# Motor-X.net
KiCad netlist of a schematic drawn in Altium Designer
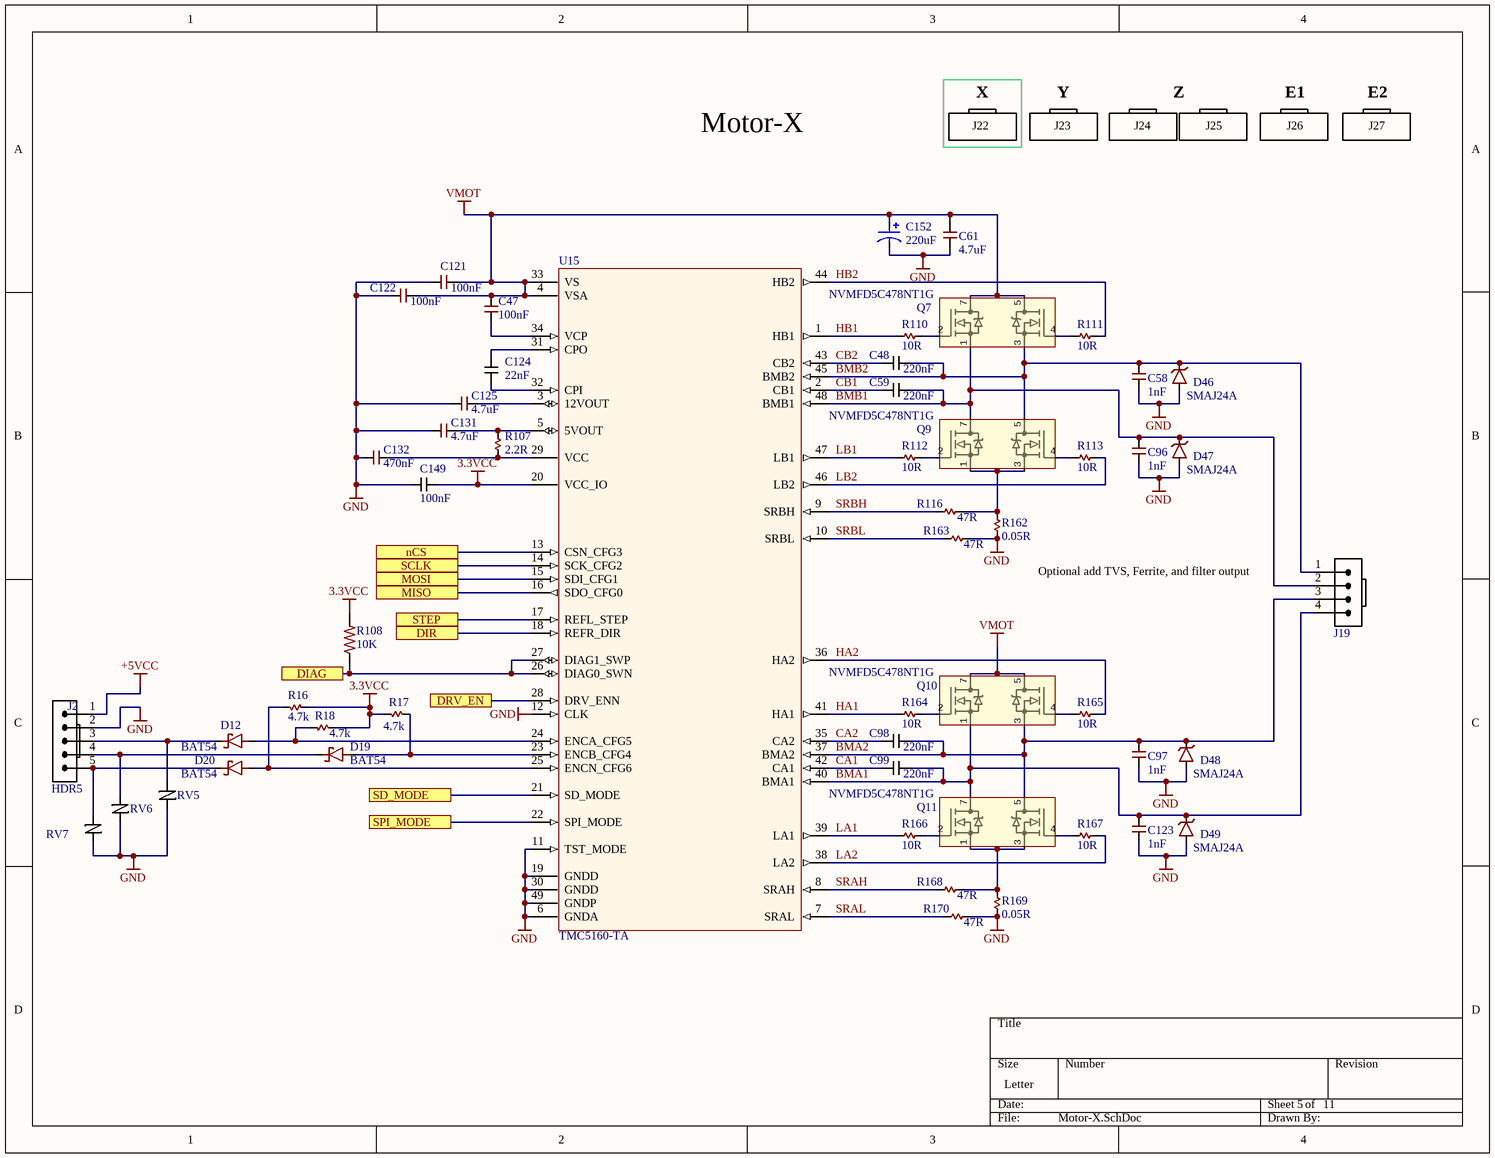
[diagram p0: Motor-X.SchDoc]

(export (version "E")
  (design (tool "Eeschema 10.0.6"))
  (components
    (comp (ref "C47")
      (value "100nF")
      (footprint "C0603")
      (description "CAP CER 0603 100nF 50V 10% X7R")
      (fields (field (name "MANUFACTURER") "Kemet") (field (name "PART") "100nF 50V X7R 0603"))
      (libsource (lib "Capacitors") (part "100nF 0603 50V X7R"))
    )
    (comp (ref "C48")
      (value "220nF")
      (footprint "C0603")
      (description "CAP CER 0.22UF 50V X7R 0603")
      (fields (field (name "MANUFACTURER") "TDK"))
      (libsource (lib "Capacitors") (part "220nF 50V X7R 0603"))
    )
    (comp (ref "C58")
      (value "1nF")
      (footprint "C0603")
      (description "CAP CER 0603  1nF 50v 10% X7R")
      (fields (field (name "MANUFACTURER") "Kemet") (field (name "TOLERANCE") "+/- 10%"))
      (libsource (lib "Capacitors") (part "1nF 50V X7R 0603"))
    )
    (comp (ref "C59")
      (value "220nF")
      (footprint "C0603")
      (description "CAP CER 0.22UF 50V X7R 0603")
      (fields (field (name "MANUFACTURER") "TDK"))
      (libsource (lib "Capacitors") (part "220nF 50V X7R 0603"))
    )
    (comp (ref "C61")
      (value "4.7uF")
      (footprint "C1206")
      (description "CAP CER 1206 4.7uF 50V 10% X5R")
      (fields (field (name "MANUFACTURER") "Kemet") (field (name "PART") "4.7uF 50V X5R 1206"))
      (libsource (lib "Capacitors") (part "4.7uF 1206 50V X5R"))
    )
    (comp (ref "C96")
      (value "1nF")
      (footprint "C0603")
      (description "CAP CER 0603  1nF 50v 10% X7R")
      (fields (field (name "MANUFACTURER") "Kemet") (field (name "TOLERANCE") "+/- 10%"))
      (libsource (lib "Capacitors") (part "1nF 50V X7R 0603"))
    )
    (comp (ref "C97")
      (value "1nF")
      (footprint "C0603")
      (description "CAP CER 0603  1nF 50v 10% X7R")
      (fields (field (name "MANUFACTURER") "Kemet") (field (name "TOLERANCE") "+/- 10%"))
      (libsource (lib "Capacitors") (part "1nF 50V X7R 0603"))
    )
    (comp (ref "C98")
      (value "220nF")
      (footprint "C0603")
      (description "CAP CER 0.22UF 50V X7R 0603")
      (fields (field (name "MANUFACTURER") "TDK"))
      (libsource (lib "Capacitors") (part "220nF 50V X7R 0603"))
    )
    (comp (ref "C99")
      (value "220nF")
      (footprint "C0603")
      (description "CAP CER 0.22UF 50V X7R 0603")
      (fields (field (name "MANUFACTURER") "TDK"))
      (libsource (lib "Capacitors") (part "220nF 50V X7R 0603"))
    )
    (comp (ref "C121")
      (value "100nF")
      (footprint "C0603")
      (description "CAP CER 0603 100nF 50V 10% X7R")
      (fields (field (name "MANUFACTURER") "Kemet") (field (name "PART") "100nF 50V X7R 0603"))
      (libsource (lib "Capacitors") (part "100nF 0603 50V X7R"))
    )
    (comp (ref "C122")
      (value "100nF")
      (footprint "C0603")
      (description "CAP CER 0603 100nF 50V 10% X7R")
      (fields (field (name "MANUFACTURER") "Kemet") (field (name "PART") "100nF 50V X7R 0603"))
      (libsource (lib "Capacitors") (part "100nF 0603 50V X7R"))
    )
    (comp (ref "C123")
      (value "1nF")
      (footprint "C0603")
      (description "CAP CER 0603  1nF 50v 10% X7R")
      (fields (field (name "MANUFACTURER") "Kemet") (field (name "TOLERANCE") "+/- 10%"))
      (libsource (lib "Capacitors") (part "1nF 50V X7R 0603"))
    )
    (comp (ref "C124")
      (value "22nF")
      (footprint "C0603")
      (description "CAP CER 0.022UF 100V X7R 0603")
      (fields (field (name "MANUFACTURER") "Kemet"))
      (libsource (lib "Capacitors") (part "22nF 100V X7R 0603"))
    )
    (comp (ref "C125")
      (value "4.7uF")
      (footprint "C1206")
      (description "CAP CER 1206 4.7uF 50V 10% X5R")
      (fields (field (name "MANUFACTURER") "Kemet") (field (name "PART") "4.7uF 50V X5R 1206"))
      (libsource (lib "Capacitors") (part "4.7uF 1206 50V X5R"))
    )
    (comp (ref "C131")
      (value "4.7uF")
      (footprint "C0603")
      (description "CAP CER 4.7UF 6.3V X7R 0603")
      (fields (field (name "MANUFACTURER") "Samsung") (field (name "TOLERANCE") "10%"))
      (libsource (lib "Capacitors") (part "4.7uF 0603 6.3V X7R"))
    )
    (comp (ref "C132")
      (value "470nF")
      (footprint "C0402")
      (description "470nF 6.3v C0402 - GRM155R60J474KE19D")
      (fields (field (name "TOLERANCE") "10%") (field (name "MANUFACTURER") "Murata"))
      (libsource (lib "Capacitors") (part "470nF 0402 6.3V X5R"))
    )
    (comp (ref "C149")
      (value "100nF")
      (footprint "C0201 Large Pads")
      (description "CAP CER 0.1UF 6.3V 10% X5R 0201")
      (fields (field (name "MANUFACTURER") "Samsung") (field (name "TOLERANCE") "10%"))
      (libsource (lib "Capacitors") (part "100nF 6.3V X5R 0201"))
    )
    (comp (ref "C152")
      (value "220uF")
      (footprint "CAP10X10")
      (description "CAP ALUM 220UF 20% 50V SMD")
      (fields (field (name "MANUFACTURER") "Nichicon") (field (name "TOLERANCE") "20%"))
      (libsource (lib "Capacitors") (part "220uF Al-El 50V"))
    )
    (comp (ref "D12")
      (value "BAT54")
      (footprint "SOD523_IPC")
      (description "DIODE SCHOTTKY 30V 200MA SOD523")
      (fields (field (name "MANUFACTURER") "Diodes Incorporated") (field (name "PART") "Schottky Diode"))
      (libsource (lib "Diodes") (part "BAT54WX"))
    )
    (comp (ref "D19")
      (value "BAT54")
      (footprint "SOD523_IPC")
      (description "DIODE SCHOTTKY 30V 200MA SOD523")
      (fields (field (name "MANUFACTURER") "Diodes Incorporated") (field (name "PART") "Schottky Diode"))
      (libsource (lib "Diodes") (part "BAT54WX"))
    )
    (comp (ref "D20")
      (value "BAT54")
      (footprint "SOD523_IPC")
      (description "DIODE SCHOTTKY 30V 200MA SOD523")
      (fields (field (name "MANUFACTURER") "Diodes Incorporated") (field (name "PART") "Schottky Diode"))
      (libsource (lib "Diodes") (part "BAT54WX"))
    )
    (comp (ref "D46")
      (value "SMAJ24A")
      (footprint "SMA-SM")
      (description "TVS DIODE 24V 38.9V SMA")
      (fields (field (name "MANUFACTURER") "Bourns Inc"))
      (libsource (lib "Diodes") (part "SMAJ24A"))
    )
    (comp (ref "D47")
      (value "SMAJ24A")
      (footprint "SMA-SM")
      (description "TVS DIODE 24V 38.9V SMA")
      (fields (field (name "MANUFACTURER") "Bourns Inc"))
      (libsource (lib "Diodes") (part "SMAJ24A"))
    )
    (comp (ref "D48")
      (value "SMAJ24A")
      (footprint "SMA-SM")
      (description "TVS DIODE 24V 38.9V SMA")
      (fields (field (name "MANUFACTURER") "Bourns Inc"))
      (libsource (lib "Diodes") (part "SMAJ24A"))
    )
    (comp (ref "D49")
      (value "SMAJ24A")
      (footprint "SMA-SM")
      (description "TVS DIODE 24V 38.9V SMA")
      (fields (field (name "MANUFACTURER") "Bourns Inc"))
      (libsource (lib "Diodes") (part "SMAJ24A"))
    )
    (comp (ref "J2")
      (value "HDR5")
      (footprint "70543-04_PIN-IN-PASTE")
      (description "5 Positions Header, Shrouded Connector 0.100\" (2.54mm) Through Hole Gold - Pin in Paste")
      (fields (field (name "MANUFACTURER") "Molex") (field (name "PART") "5 Pin Conn VERT"))
      (libsource (lib "Connectors") (part "CONN 5POS VERT 0.1{dblquote} SHRD LOCKING PIP"))
    )
    (comp (ref "J19")
      (value "Molex 0705430003")
      (footprint "4POL254 PIN-IN-PASTE")
      (description "Molex 4 Pin Clip Connector - Pin In Paste footprint")
      (libsource (lib "Connectors") (part "Molex 0705430003 PIP"))
    )
    (comp (ref "Q7")
      (value "NVMFD5C478NT1G")
      (footprint "SO8FL-Dual (DFN8 5x6, 1.26P Dual Flag)")
      (description "40V 17 MOHM T6 S08FL DUAL")
      (fields (field (name "MANUFACTURER") "ON Semiconductor") (field (name "TOLERANCE") "-NA-"))
      (libsource (lib "Transistors") (part "NVMFD5C478NT1G"))
    )
    (comp (ref "Q9")
      (value "NVMFD5C478NT1G")
      (footprint "SO8FL-Dual (DFN8 5x6, 1.26P Dual Flag)")
      (description "40V 17 MOHM T6 S08FL DUAL")
      (fields (field (name "MANUFACTURER") "ON Semiconductor") (field (name "TOLERANCE") "-NA-"))
      (libsource (lib "Transistors") (part "NVMFD5C478NT1G"))
    )
    (comp (ref "Q10")
      (value "NVMFD5C478NT1G")
      (footprint "SO8FL-Dual (DFN8 5x6, 1.26P Dual Flag)")
      (description "40V 17 MOHM T6 S08FL DUAL")
      (fields (field (name "MANUFACTURER") "ON Semiconductor") (field (name "TOLERANCE") "-NA-"))
      (libsource (lib "Transistors") (part "NVMFD5C478NT1G"))
    )
    (comp (ref "Q11")
      (value "NVMFD5C478NT1G")
      (footprint "SO8FL-Dual (DFN8 5x6, 1.26P Dual Flag)")
      (description "40V 17 MOHM T6 S08FL DUAL")
      (fields (field (name "MANUFACTURER") "ON Semiconductor") (field (name "TOLERANCE") "-NA-"))
      (libsource (lib "Transistors") (part "NVMFD5C478NT1G"))
    )
    (comp (ref "R16")
      (value "4.7k")
      (footprint "R0402")
      (description "RES SMD 4.7K OHM 1% 1/16W 0402")
      (fields (field (name "MANUFACTURER") "YAGEO") (field (name "PART") "4.7k 1% 0402"))
      (libsource (lib "Resistors") (part "4.7k 1% 0402"))
    )
    (comp (ref "R17")
      (value "4.7k")
      (footprint "R0402")
      (description "RES SMD 4.7K OHM 1% 1/16W 0402")
      (fields (field (name "MANUFACTURER") "YAGEO") (field (name "PART") "4.7k 1% 0402"))
      (libsource (lib "Resistors") (part "4.7k 1% 0402"))
    )
    (comp (ref "R18")
      (value "4.7k")
      (footprint "R0402")
      (description "RES SMD 4.7K OHM 1% 1/16W 0402")
      (fields (field (name "MANUFACTURER") "YAGEO") (field (name "PART") "4.7k 1% 0402"))
      (libsource (lib "Resistors") (part "4.7k 1% 0402"))
    )
    (comp (ref "R107")
      (value "2.2R")
      (footprint "R0402")
      (description "RES SMD 2.2 OHM 5% 1/16W 0402")
      (fields (field (name "MANUFACTURER") "Yageo") (field (name "TOLERANCE") "+/- 5%"))
      (libsource (lib "Resistors") (part "2.2R 5% 0402"))
    )
    (comp (ref "R108")
      (value "10K")
      (footprint "R0402")
      (description "RES SMD 10K OHM 1% 1/16W 0402")
      (fields (field (name "MANUFACTURER") "Yageo") (field (name "PART") "10k 1% 0402"))
      (libsource (lib "3Delight") (part "RC0402FR-0710KP"))
    )
    (comp (ref "R110")
      (value "10R")
      (footprint "R0402")
      (description "RES SMD 10 OHM 1% 1/16W 0402")
      (fields (field (name "MANUFACTURER") "Yageo") (field (name "PART") "10R 1% 0402"))
      (libsource (lib "Resistors") (part "10R 1% 0402"))
    )
    (comp (ref "R111")
      (value "10R")
      (footprint "R0402")
      (description "RES SMD 10 OHM 1% 1/16W 0402")
      (fields (field (name "MANUFACTURER") "Yageo") (field (name "PART") "10R 1% 0402"))
      (libsource (lib "Resistors") (part "10R 1% 0402"))
    )
    (comp (ref "R112")
      (value "10R")
      (footprint "R0402")
      (description "RES SMD 10 OHM 1% 1/16W 0402")
      (fields (field (name "MANUFACTURER") "Yageo") (field (name "PART") "10R 1% 0402"))
      (libsource (lib "Resistors") (part "10R 1% 0402"))
    )
    (comp (ref "R113")
      (value "10R")
      (footprint "R0402")
      (description "RES SMD 10 OHM 1% 1/16W 0402")
      (fields (field (name "MANUFACTURER") "Yageo") (field (name "PART") "10R 1% 0402"))
      (libsource (lib "Resistors") (part "10R 1% 0402"))
    )
    (comp (ref "R116")
      (value "47R")
      (footprint "R0402")
      (description "RES 47 OHM 1% 1/16W 0402")
      (fields (field (name "MANUFACTURER") "Vishay Dale") (field (name "TOLERANCE") "+/- 1%"))
      (libsource (lib "Resistors") (part "47R 1% 0402"))
    )
    (comp (ref "R162")
      (value "0.05R")
      (footprint "R2512")
      (description "RES 0.05 OHM 1% 2W 2512")
      (fields (field (name "MANUFACTURER") "Stackpole") (field (name "TOLERANCE") "+/- 1%"))
      (libsource (lib "Resistors") (part "0.05R 1% 2512"))
    )
    (comp (ref "R163")
      (value "47R")
      (footprint "R0402")
      (description "RES 47 OHM 1% 1/16W 0402")
      (fields (field (name "MANUFACTURER") "Vishay Dale") (field (name "TOLERANCE") "+/- 1%"))
      (libsource (lib "Resistors") (part "47R 1% 0402"))
    )
    (comp (ref "R164")
      (value "10R")
      (footprint "R0402")
      (description "RES SMD 10 OHM 1% 1/16W 0402")
      (fields (field (name "MANUFACTURER") "Yageo") (field (name "PART") "10R 1% 0402"))
      (libsource (lib "Resistors") (part "10R 1% 0402"))
    )
    (comp (ref "R165")
      (value "10R")
      (footprint "R0402")
      (description "RES SMD 10 OHM 1% 1/16W 0402")
      (fields (field (name "MANUFACTURER") "Yageo") (field (name "PART") "10R 1% 0402"))
      (libsource (lib "Resistors") (part "10R 1% 0402"))
    )
    (comp (ref "R166")
      (value "10R")
      (footprint "R0402")
      (description "RES SMD 10 OHM 1% 1/16W 0402")
      (fields (field (name "MANUFACTURER") "Yageo") (field (name "PART") "10R 1% 0402"))
      (libsource (lib "Resistors") (part "10R 1% 0402"))
    )
    (comp (ref "R167")
      (value "10R")
      (footprint "R0402")
      (description "RES SMD 10 OHM 1% 1/16W 0402")
      (fields (field (name "MANUFACTURER") "Yageo") (field (name "PART") "10R 1% 0402"))
      (libsource (lib "Resistors") (part "10R 1% 0402"))
    )
    (comp (ref "R168")
      (value "47R")
      (footprint "R0402")
      (description "RES 47 OHM 1% 1/16W 0402")
      (fields (field (name "MANUFACTURER") "Vishay Dale") (field (name "TOLERANCE") "+/- 1%"))
      (libsource (lib "Resistors") (part "47R 1% 0402"))
    )
    (comp (ref "R169")
      (value "0.05R")
      (footprint "R2512")
      (description "RES 0.05 OHM 1% 2W 2512")
      (fields (field (name "MANUFACTURER") "Stackpole") (field (name "TOLERANCE") "+/- 1%"))
      (libsource (lib "Resistors") (part "0.05R 1% 2512"))
    )
    (comp (ref "R170")
      (value "47R")
      (footprint "R0402")
      (description "RES 47 OHM 1% 1/16W 0402")
      (fields (field (name "MANUFACTURER") "Vishay Dale") (field (name "TOLERANCE") "+/- 1%"))
      (libsource (lib "Resistors") (part "47R 1% 0402"))
    )
    (comp (ref "RV5")
      (value "AVRM0603C6R8NT101N")
      (footprint "C0201 Large Pads")
      (description "VARISTOR 6.8V 10A 0201")
      (fields (field (name "MANUFACTURER") "TDK") (field (name "TOLERANCE") "-NA-"))
      (libsource (lib "ESD") (part "AVRM0603C6R8NT101N"))
    )
    (comp (ref "RV6")
      (value "AVRM0603C6R8NT101N")
      (footprint "C0201 Large Pads")
      (description "VARISTOR 6.8V 10A 0201")
      (fields (field (name "MANUFACTURER") "TDK") (field (name "TOLERANCE") "-NA-"))
      (libsource (lib "ESD") (part "AVRM0603C6R8NT101N"))
    )
    (comp (ref "RV7")
      (value "AVRM0603C6R8NT101N")
      (footprint "C0201 Large Pads")
      (description "VARISTOR 6.8V 10A 0201")
      (fields (field (name "MANUFACTURER") "TDK") (field (name "TOLERANCE") "-NA-"))
      (libsource (lib "ESD") (part "AVRM0603C6R8NT101N"))
    )
    (comp (ref "U15")
      (value "TMC5160-TA")
      (footprint "TQFP48-EP")
      (description "IC STEPPER MOTOR DVR TQFP48-EP")
      (fields (field (name "MANUFACTURER") "Trinamic"))
      (libsource (lib "ICs-Motor Controller") (part "TMC5160-TA"))
    )
  )
  (nets
    (net (code "1") (name "+5VCC") (class "Default")
      (node (ref "J2") (pin "1") (pinfunction "1_1") (pintype "passive"))
    )
    (net (code "2") (name "/BMA1") (class "Default")
      (node (ref "C123") (pin "2") (pinfunction "2_2") (pintype "passive"))
      (node (ref "C99") (pin "2") (pinfunction "2_2") (pintype "passive"))
      (node (ref "D49") (pin "K") (pinfunction "K_K") (pintype "passive"))
      (node (ref "J19") (pin "4") (pinfunction "4_4") (pintype "passive"))
      (node (ref "Q10") (pin "1") (pinfunction "S2_1") (pintype "passive"))
      (node (ref "Q11") (pin "7") (pinfunction "D2_7") (pintype "passive"))
      (node (ref "U15") (pin "40") (pinfunction "BMA1_40") (pintype "input"))
    )
    (net (code "3") (name "/BMA2") (class "Default")
      (node (ref "C97") (pin "2") (pinfunction "2_2") (pintype "passive"))
      (node (ref "C98") (pin "2") (pinfunction "2_2") (pintype "passive"))
      (node (ref "D48") (pin "K") (pinfunction "K_K") (pintype "passive"))
      (node (ref "J19") (pin "3") (pinfunction "3_3") (pintype "passive"))
      (node (ref "Q10") (pin "3") (pinfunction "S1_3") (pintype "passive"))
      (node (ref "Q11") (pin "5") (pinfunction "D1_5") (pintype "passive"))
      (node (ref "U15") (pin "37") (pinfunction "BMA2_37") (pintype "input"))
    )
    (net (code "4") (name "/BMB1") (class "Default")
      (node (ref "C59") (pin "2") (pinfunction "2_2") (pintype "passive"))
      (node (ref "C96") (pin "2") (pinfunction "2_2") (pintype "passive"))
      (node (ref "D47") (pin "K") (pinfunction "K_K") (pintype "passive"))
      (node (ref "J19") (pin "2") (pinfunction "2_2") (pintype "passive"))
      (node (ref "Q7") (pin "1") (pinfunction "S2_1") (pintype "passive"))
      (node (ref "Q9") (pin "7") (pinfunction "D2_7") (pintype "passive"))
      (node (ref "U15") (pin "48") (pinfunction "BMB1_48") (pintype "input"))
    )
    (net (code "5") (name "/BMB2") (class "Default")
      (node (ref "C48") (pin "2") (pinfunction "2_2") (pintype "passive"))
      (node (ref "C58") (pin "2") (pinfunction "2_2") (pintype "passive"))
      (node (ref "D46") (pin "K") (pinfunction "K_K") (pintype "passive"))
      (node (ref "J19") (pin "1") (pinfunction "1_1") (pintype "passive"))
      (node (ref "Q7") (pin "3") (pinfunction "S1_3") (pintype "passive"))
      (node (ref "Q9") (pin "5") (pinfunction "D1_5") (pintype "passive"))
      (node (ref "U15") (pin "45") (pinfunction "BMB2_45") (pintype "input"))
    )
    (net (code "6") (name "/CA1") (class "Default")
      (node (ref "C99") (pin "1") (pinfunction "1_1") (pintype "passive"))
      (node (ref "U15") (pin "42") (pinfunction "CA1_42") (pintype "input"))
    )
    (net (code "7") (name "/CA2") (class "Default")
      (node (ref "C98") (pin "1") (pinfunction "1_1") (pintype "passive"))
      (node (ref "U15") (pin "35") (pinfunction "CA2_35") (pintype "input"))
    )
    (net (code "8") (name "/CB1") (class "Default")
      (node (ref "C59") (pin "1") (pinfunction "1_1") (pintype "passive"))
      (node (ref "U15") (pin "2") (pinfunction "CB1_2") (pintype "input"))
    )
    (net (code "9") (name "/CB2") (class "Default")
      (node (ref "C48") (pin "1") (pinfunction "1_1") (pintype "passive"))
      (node (ref "U15") (pin "43") (pinfunction "CB2_43") (pintype "input"))
    )
    (net (code "10") (name "/DIAG") (class "Default")
      (node (ref "R108") (pin "1") (pinfunction "1_1") (pintype "passive"))
      (node (ref "U15") (pin "26") (pinfunction "DIAG0_SWN_26") (pintype "bidirectional"))
      (node (ref "U15") (pin "27") (pinfunction "DIAG1_SWP_27") (pintype "bidirectional"))
    )
    (net (code "11") (name "/DIR") (class "Default")
      (node (ref "U15") (pin "18") (pinfunction "REFR_DIR_18") (pintype "input"))
    )
    (net (code "12") (name "/DRV_EN") (class "Default")
      (node (ref "U15") (pin "28") (pinfunction "DRV_ENN_28") (pintype "input"))
    )
    (net (code "13") (name "/HA1") (class "Default")
      (node (ref "R164") (pin "1") (pinfunction "1_1") (pintype "passive"))
      (node (ref "U15") (pin "41") (pinfunction "HA1_41") (pintype "output"))
    )
    (net (code "14") (name "/HA2") (class "Default")
      (node (ref "R165") (pin "2") (pinfunction "2_2") (pintype "passive"))
      (node (ref "U15") (pin "36") (pinfunction "HA2_36") (pintype "output"))
    )
    (net (code "15") (name "/HB1") (class "Default")
      (node (ref "R110") (pin "1") (pinfunction "1_1") (pintype "passive"))
      (node (ref "U15") (pin "1") (pinfunction "HB1_1") (pintype "output"))
    )
    (net (code "16") (name "/HB2") (class "Default")
      (node (ref "R111") (pin "2") (pinfunction "2_2") (pintype "passive"))
      (node (ref "U15") (pin "44") (pinfunction "HB2_44") (pintype "output"))
    )
    (net (code "17") (name "/LA1") (class "Default")
      (node (ref "R166") (pin "1") (pinfunction "1_1") (pintype "passive"))
      (node (ref "U15") (pin "39") (pinfunction "LA1_39") (pintype "output"))
    )
    (net (code "18") (name "/LA2") (class "Default")
      (node (ref "R167") (pin "2") (pinfunction "2_2") (pintype "passive"))
      (node (ref "U15") (pin "38") (pinfunction "LA2_38") (pintype "output"))
    )
    (net (code "19") (name "/LB1") (class "Default")
      (node (ref "R112") (pin "1") (pinfunction "1_1") (pintype "passive"))
      (node (ref "U15") (pin "47") (pinfunction "LB1_47") (pintype "output"))
    )
    (net (code "20") (name "/LB2") (class "Default")
      (node (ref "R113") (pin "2") (pinfunction "2_2") (pintype "passive"))
      (node (ref "U15") (pin "46") (pinfunction "LB2_46") (pintype "output"))
    )
    (net (code "21") (name "/MISO") (class "Default")
      (node (ref "U15") (pin "16") (pinfunction "SDO_CFG0_16") (pintype "output"))
    )
    (net (code "22") (name "/MOSI") (class "Default")
      (node (ref "U15") (pin "15") (pinfunction "SDI_CFG1_15") (pintype "input"))
    )
    (net (code "23") (name "/SCLK") (class "Default")
      (node (ref "U15") (pin "14") (pinfunction "SCK_CFG2_14") (pintype "input"))
    )
    (net (code "24") (name "/SD_MODE") (class "Default")
      (node (ref "U15") (pin "21") (pinfunction "SD_MODE_21") (pintype "input"))
    )
    (net (code "25") (name "/SPI_MODE") (class "Default")
      (node (ref "U15") (pin "22") (pinfunction "SPI_MODE_22") (pintype "input"))
    )
    (net (code "26") (name "/SRAH") (class "Default")
      (node (ref "R168") (pin "1") (pinfunction "1_1") (pintype "passive"))
      (node (ref "U15") (pin "8") (pinfunction "SRAH_8") (pintype "input"))
    )
    (net (code "27") (name "/SRAL") (class "Default")
      (node (ref "R170") (pin "1") (pinfunction "1_1") (pintype "passive"))
      (node (ref "U15") (pin "7") (pinfunction "SRAL_7") (pintype "input"))
    )
    (net (code "28") (name "/SRBH") (class "Default")
      (node (ref "R116") (pin "1") (pinfunction "1_1") (pintype "passive"))
      (node (ref "U15") (pin "9") (pinfunction "SRBH_9") (pintype "input"))
    )
    (net (code "29") (name "/SRBL") (class "Default")
      (node (ref "R163") (pin "1") (pinfunction "1_1") (pintype "passive"))
      (node (ref "U15") (pin "10") (pinfunction "SRBL_10") (pintype "input"))
    )
    (net (code "30") (name "/STEP") (class "Default")
      (node (ref "U15") (pin "17") (pinfunction "REFL_STEP_17") (pintype "input"))
    )
    (net (code "31") (name "/nCS") (class "Default")
      (node (ref "U15") (pin "13") (pinfunction "CSN_CFG3_13") (pintype "input"))
    )
    (net (code "32") (name "3.3VCC") (class "Default")
      (node (ref "C149") (pin "2") (pinfunction "2_2") (pintype "passive"))
      (node (ref "R108") (pin "2") (pinfunction "2_2") (pintype "passive"))
      (node (ref "R16") (pin "2") (pinfunction "2_2") (pintype "passive"))
      (node (ref "R17") (pin "1") (pinfunction "1_1") (pintype "passive"))
      (node (ref "R18") (pin "2") (pinfunction "2_2") (pintype "passive"))
      (node (ref "U15") (pin "20") (pinfunction "VCC_IO_20") (pintype "power_in"))
    )
    (net (code "33") (name "GND") (class "Default")
      (node (ref "C121") (pin "1") (pinfunction "1_1") (pintype "passive"))
      (node (ref "C122") (pin "1") (pinfunction "1_1") (pintype "passive"))
      (node (ref "C123") (pin "1") (pinfunction "1_1") (pintype "passive"))
      (node (ref "C125") (pin "1") (pinfunction "1_1") (pintype "passive"))
      (node (ref "C131") (pin "1") (pinfunction "1_1") (pintype "passive"))
      (node (ref "C132") (pin "1") (pinfunction "1_1") (pintype "passive"))
      (node (ref "C149") (pin "1") (pinfunction "1_1") (pintype "passive"))
      (node (ref "C152") (pin "2") (pinfunction "2_2") (pintype "passive"))
      (node (ref "C58") (pin "1") (pinfunction "1_1") (pintype "passive"))
      (node (ref "C61") (pin "1") (pinfunction "1_1") (pintype "passive"))
      (node (ref "C96") (pin "1") (pinfunction "1_1") (pintype "passive"))
      (node (ref "C97") (pin "1") (pinfunction "1_1") (pintype "passive"))
      (node (ref "D46") (pin "A") (pinfunction "A_A") (pintype "passive"))
      (node (ref "D47") (pin "A") (pinfunction "A_A") (pintype "passive"))
      (node (ref "D48") (pin "A") (pinfunction "A_A") (pintype "passive"))
      (node (ref "D49") (pin "A") (pinfunction "A_A") (pintype "passive"))
      (node (ref "J2") (pin "2") (pinfunction "2_2") (pintype "passive"))
      (node (ref "R162") (pin "1") (pinfunction "1_1") (pintype "passive"))
      (node (ref "R163") (pin "2") (pinfunction "2_2") (pintype "passive"))
      (node (ref "R169") (pin "1") (pinfunction "1_1") (pintype "passive"))
      (node (ref "R170") (pin "2") (pinfunction "2_2") (pintype "passive"))
      (node (ref "RV5") (pin "2") (pinfunction "2_2") (pintype "power_in"))
      (node (ref "RV6") (pin "2") (pinfunction "2_2") (pintype "power_in"))
      (node (ref "RV7") (pin "2") (pinfunction "2_2") (pintype "power_in"))
      (node (ref "U15") (pin "11") (pinfunction "TST_MODE_11") (pintype "input"))
      (node (ref "U15") (pin "12") (pinfunction "CLK_12") (pintype "input"))
      (node (ref "U15") (pin "19") (pinfunction "GNDD_19") (pintype "power_in"))
      (node (ref "U15") (pin "30") (pinfunction "GNDD_30") (pintype "power_in"))
      (node (ref "U15") (pin "49") (pinfunction "GNDP_49") (pintype "power_in"))
      (node (ref "U15") (pin "6") (pinfunction "GNDA_6") (pintype "power_in"))
    )
    (net (code "34") (name "Net-(D12-PadK)") (class "Default")
      (node (ref "D12") (pin "K") (pinfunction "K_K") (pintype "passive"))
      (node (ref "J2") (pin "3") (pinfunction "3_3") (pintype "passive"))
      (node (ref "RV5") (pin "1") (pinfunction "1_1") (pintype "power_in"))
    )
    (net (code "35") (name "Net-(D19-PadK)") (class "Default")
      (node (ref "D19") (pin "K") (pinfunction "K_K") (pintype "passive"))
      (node (ref "J2") (pin "4") (pinfunction "4_4") (pintype "passive"))
      (node (ref "RV6") (pin "1") (pinfunction "1_1") (pintype "power_in"))
    )
    (net (code "36") (name "Net-(D20-PadK)") (class "Default")
      (node (ref "D20") (pin "K") (pinfunction "K_K") (pintype "passive"))
      (node (ref "J2") (pin "5") (pinfunction "5_5") (pintype "passive"))
      (node (ref "RV7") (pin "1") (pinfunction "1_1") (pintype "power_in"))
    )
    (net (code "37") (name "Net-(Q7-G1)") (class "Default")
      (node (ref "Q7") (pin "4") (pinfunction "G1_4") (pintype "passive"))
      (node (ref "R111") (pin "1") (pinfunction "1_1") (pintype "passive"))
    )
    (net (code "38") (name "Net-(Q7-G2)") (class "Default")
      (node (ref "Q7") (pin "2") (pinfunction "G2_2") (pintype "passive"))
      (node (ref "R110") (pin "2") (pinfunction "2_2") (pintype "passive"))
    )
    (net (code "39") (name "Net-(Q9-G1)") (class "Default")
      (node (ref "Q9") (pin "4") (pinfunction "G1_4") (pintype "passive"))
      (node (ref "R113") (pin "1") (pinfunction "1_1") (pintype "passive"))
    )
    (net (code "40") (name "Net-(Q9-G2)") (class "Default")
      (node (ref "Q9") (pin "2") (pinfunction "G2_2") (pintype "passive"))
      (node (ref "R112") (pin "2") (pinfunction "2_2") (pintype "passive"))
    )
    (net (code "41") (name "Net-(Q9-S1)") (class "Default")
      (node (ref "Q9") (pin "1") (pinfunction "S2_1") (pintype "passive"))
      (node (ref "Q9") (pin "3") (pinfunction "S1_3") (pintype "passive"))
      (node (ref "R116") (pin "2") (pinfunction "2_2") (pintype "passive"))
      (node (ref "R162") (pin "2") (pinfunction "2_2") (pintype "passive"))
    )
    (net (code "42") (name "Net-(Q10-G1)") (class "Default")
      (node (ref "Q10") (pin "4") (pinfunction "G1_4") (pintype "passive"))
      (node (ref "R165") (pin "1") (pinfunction "1_1") (pintype "passive"))
    )
    (net (code "43") (name "Net-(Q10-G2)") (class "Default")
      (node (ref "Q10") (pin "2") (pinfunction "G2_2") (pintype "passive"))
      (node (ref "R164") (pin "2") (pinfunction "2_2") (pintype "passive"))
    )
    (net (code "44") (name "Net-(Q11-G1)") (class "Default")
      (node (ref "Q11") (pin "4") (pinfunction "G1_4") (pintype "passive"))
      (node (ref "R167") (pin "1") (pinfunction "1_1") (pintype "passive"))
    )
    (net (code "45") (name "Net-(Q11-G2)") (class "Default")
      (node (ref "Q11") (pin "2") (pinfunction "G2_2") (pintype "passive"))
      (node (ref "R166") (pin "2") (pinfunction "2_2") (pintype "passive"))
    )
    (net (code "46") (name "Net-(Q11-S1)") (class "Default")
      (node (ref "Q11") (pin "1") (pinfunction "S2_1") (pintype "passive"))
      (node (ref "Q11") (pin "3") (pinfunction "S1_3") (pintype "passive"))
      (node (ref "R168") (pin "2") (pinfunction "2_2") (pintype "passive"))
      (node (ref "R169") (pin "2") (pinfunction "2_2") (pintype "passive"))
    )
    (net (code "47") (name "Net-(U15-5VOUT)") (class "Default")
      (node (ref "C131") (pin "2") (pinfunction "2_2") (pintype "passive"))
      (node (ref "R107") (pin "2") (pinfunction "2_2") (pintype "passive"))
      (node (ref "U15") (pin "5") (pinfunction "5VOUT_5") (pintype "bidirectional"))
    )
    (net (code "48") (name "Net-(U15-12VOUT)") (class "Default")
      (node (ref "C125") (pin "2") (pinfunction "2_2") (pintype "passive"))
      (node (ref "U15") (pin "3") (pinfunction "12VOUT_3") (pintype "bidirectional"))
    )
    (net (code "49") (name "Net-(U15-CPI)") (class "Default")
      (node (ref "C124") (pin "1") (pinfunction "1_1") (pintype "passive"))
      (node (ref "U15") (pin "32") (pinfunction "CPI_32") (pintype "input"))
    )
    (net (code "50") (name "Net-(U15-CPO)") (class "Default")
      (node (ref "C124") (pin "2") (pinfunction "2_2") (pintype "passive"))
      (node (ref "U15") (pin "31") (pinfunction "CPO_31") (pintype "input"))
    )
    (net (code "51") (name "Net-(U15-ENCA_CFG5)") (class "Default")
      (node (ref "D12") (pin "A") (pinfunction "A_A") (pintype "passive"))
      (node (ref "R18") (pin "1") (pinfunction "1_1") (pintype "passive"))
      (node (ref "U15") (pin "24") (pinfunction "ENCA_CFG5_24") (pintype "input"))
    )
    (net (code "52") (name "Net-(U15-ENCB_CFG4)") (class "Default")
      (node (ref "D19") (pin "A") (pinfunction "A_A") (pintype "passive"))
      (node (ref "R17") (pin "2") (pinfunction "2_2") (pintype "passive"))
      (node (ref "U15") (pin "23") (pinfunction "ENCB_CFG4_23") (pintype "input"))
    )
    (net (code "53") (name "Net-(U15-ENCN_CFG6)") (class "Default")
      (node (ref "D20") (pin "A") (pinfunction "A_A") (pintype "passive"))
      (node (ref "R16") (pin "1") (pinfunction "1_1") (pintype "passive"))
      (node (ref "U15") (pin "25") (pinfunction "ENCN_CFG6_25") (pintype "input"))
    )
    (net (code "54") (name "Net-(U15-VCC)") (class "Default")
      (node (ref "C132") (pin "2") (pinfunction "2_2") (pintype "passive"))
      (node (ref "R107") (pin "1") (pinfunction "1_1") (pintype "passive"))
      (node (ref "U15") (pin "29") (pinfunction "VCC_29") (pintype "power_in"))
    )
    (net (code "55") (name "Net-(U15-VCP)") (class "Default")
      (node (ref "C47") (pin "1") (pinfunction "1_1") (pintype "passive"))
      (node (ref "U15") (pin "34") (pinfunction "VCP_34") (pintype "input"))
    )
    (net (code "56") (name "VMOT") (class "Default")
      (node (ref "C121") (pin "2") (pinfunction "2_2") (pintype "passive"))
      (node (ref "C122") (pin "2") (pinfunction "2_2") (pintype "passive"))
      (node (ref "C152") (pin "1") (pinfunction "1_1") (pintype "passive"))
      (node (ref "C47") (pin "2") (pinfunction "2_2") (pintype "passive"))
      (node (ref "C61") (pin "2") (pinfunction "2_2") (pintype "passive"))
      (node (ref "Q10") (pin "5") (pinfunction "D1_5") (pintype "passive"))
      (node (ref "Q10") (pin "7") (pinfunction "D2_7") (pintype "passive"))
      (node (ref "Q7") (pin "5") (pinfunction "D1_5") (pintype "passive"))
      (node (ref "Q7") (pin "7") (pinfunction "D2_7") (pintype "passive"))
      (node (ref "U15") (pin "33") (pinfunction "VS_33") (pintype "power_in"))
      (node (ref "U15") (pin "4") (pinfunction "VSA_4") (pintype "power_in"))
    )
  )
)
